# main_board.net
KiCad netlist of a schematic drawn in EAGLE
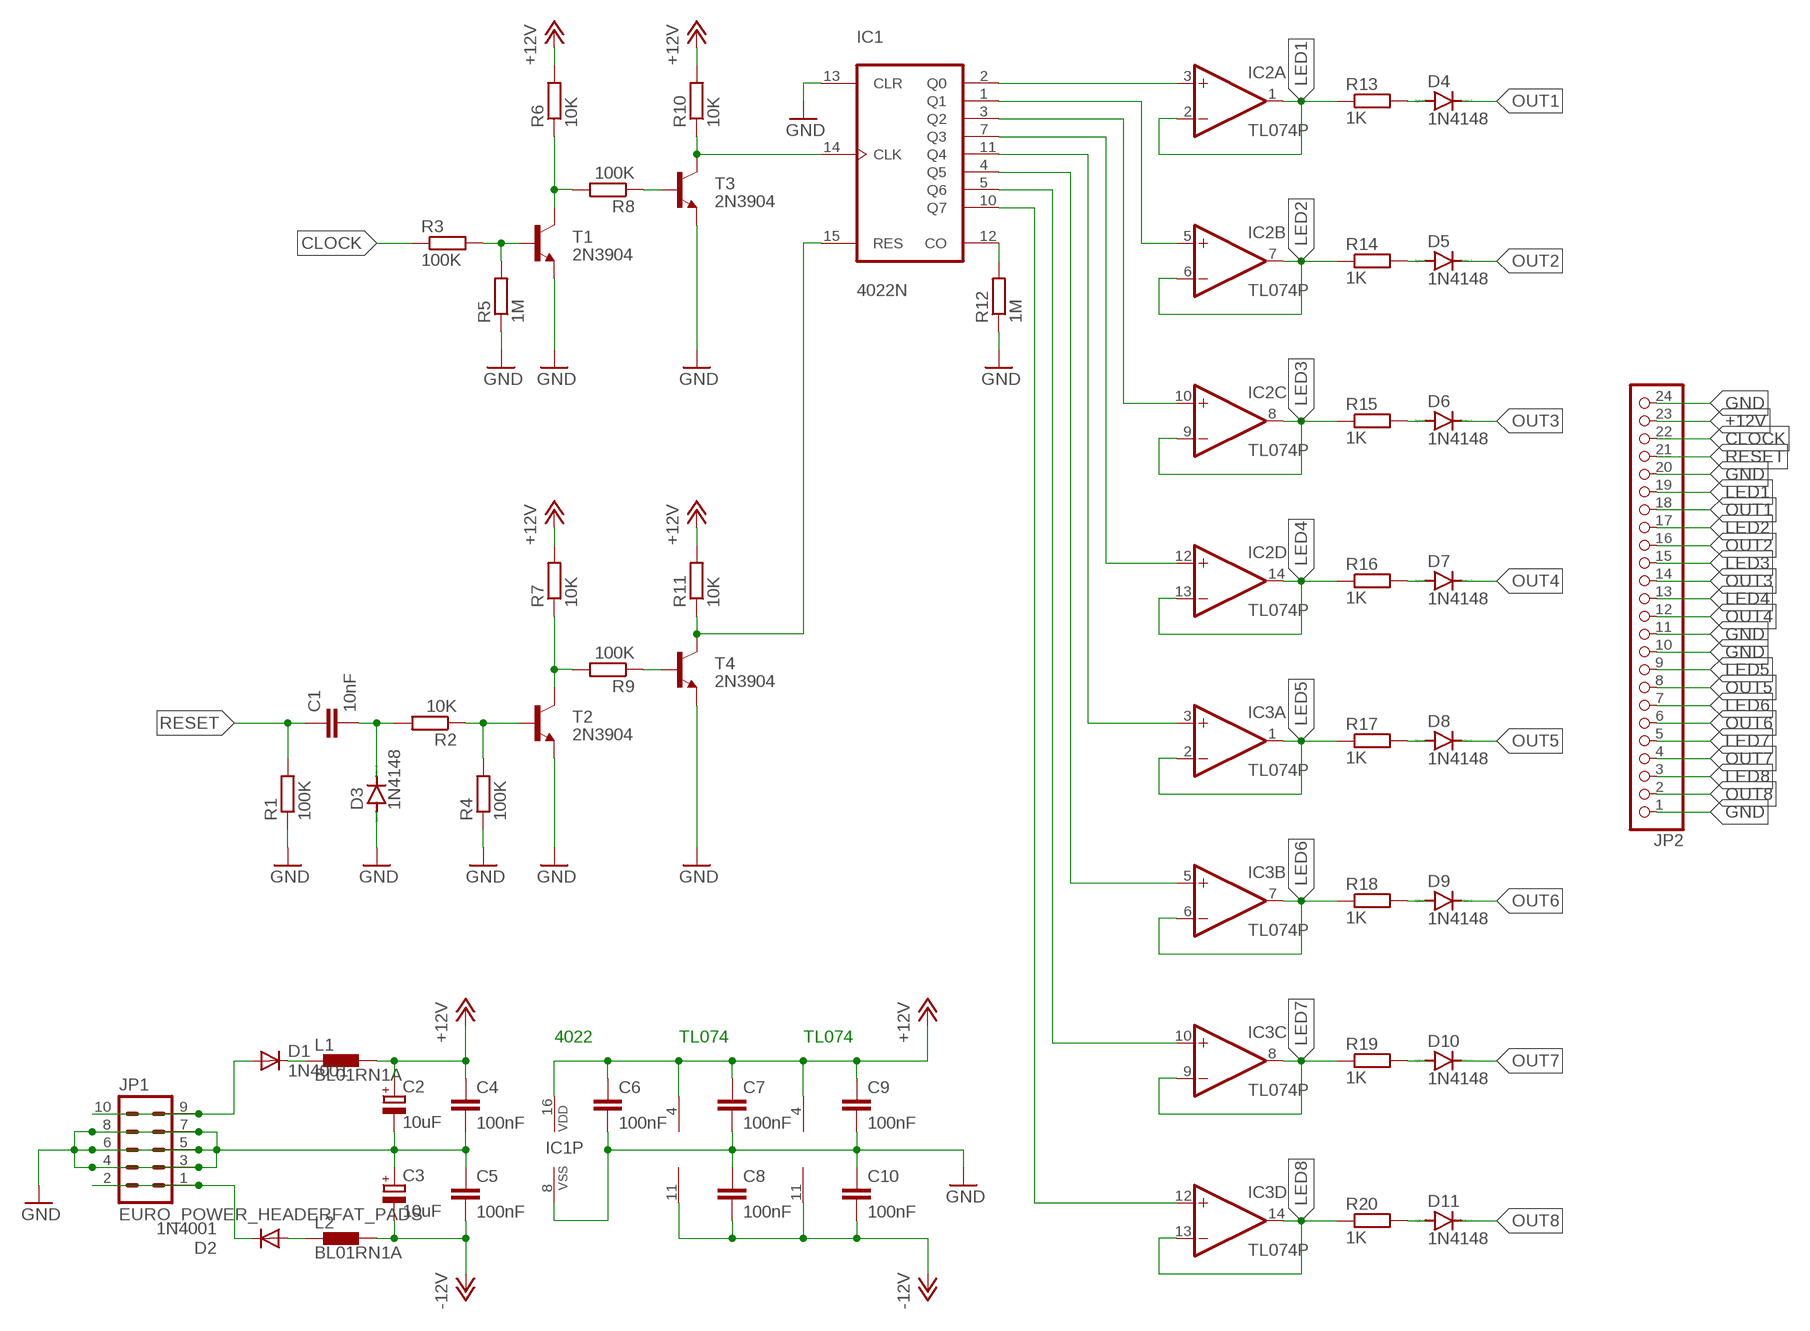
[diagram p0: schematic, sheet 1]

(export (version "E")
  (design (tool "Eeschema 10.0.6"))
  (components
    (comp (ref "C1")
      (value "10nF")
      (footprint "eagle-import:C025-024X044")
      (fields (field (name "MF") "MULTICOMP") (field (name "MPN") "MC0805Y103M500A2.54MM"))
      (libsource (lib "eagle-import") (part "C-EU025-024X044"))
    )
    (comp (ref "C2")
      (value "10uF")
      (footprint "eagle-import:E2,5-6E")
      (fields (field (name "MF") "RUBYCON") (field (name "MPN") "35ZLG10MEFC5X7"))
      (libsource (lib "eagle-import") (part "CPOL-EUE2,5-6E"))
    )
    (comp (ref "C3")
      (value "10uF")
      (footprint "eagle-import:E2,5-6E")
      (fields (field (name "MF") "RUBYCON") (field (name "MPN") "35ZLG10MEFC5X7"))
      (libsource (lib "eagle-import") (part "CPOL-EUE2,5-6E"))
    )
    (comp (ref "C4")
      (value "100nF")
      (footprint "eagle-import:C025-024X044")
      (fields (field (name "MF") "EPCOS") (field (name "MPN") "B32529C0104J289"))
      (libsource (lib "eagle-import") (part "C-EU025-024X044"))
    )
    (comp (ref "C5")
      (value "100nF")
      (footprint "eagle-import:C025-024X044")
      (fields (field (name "MF") "EPCOS") (field (name "MPN") "B32529C0104J289"))
      (libsource (lib "eagle-import") (part "C-EU025-024X044"))
    )
    (comp (ref "C6")
      (value "100nF")
      (footprint "eagle-import:C025-024X044")
      (fields (field (name "MF") "EPCOS") (field (name "MPN") "B32529C0104J289"))
      (libsource (lib "eagle-import") (part "C-EU025-024X044"))
    )
    (comp (ref "C7")
      (value "100nF")
      (footprint "eagle-import:C025-024X044")
      (fields (field (name "MF") "EPCOS") (field (name "MPN") "B32529C0104J289"))
      (libsource (lib "eagle-import") (part "C-EU025-024X044"))
    )
    (comp (ref "C8")
      (value "100nF")
      (footprint "eagle-import:C025-024X044")
      (fields (field (name "MF") "EPCOS") (field (name "MPN") "B32529C0104J289"))
      (libsource (lib "eagle-import") (part "C-EU025-024X044"))
    )
    (comp (ref "C9")
      (value "100nF")
      (footprint "eagle-import:C025-024X044")
      (fields (field (name "MF") "EPCOS") (field (name "MPN") "B32529C0104J289"))
      (libsource (lib "eagle-import") (part "C-EU025-024X044"))
    )
    (comp (ref "C10")
      (value "100nF")
      (footprint "eagle-import:C025-024X044")
      (fields (field (name "MF") "EPCOS") (field (name "MPN") "B32529C0104J289"))
      (libsource (lib "eagle-import") (part "C-EU025-024X044"))
    )
    (comp (ref "D1")
      (value "1N4001")
      (footprint "eagle-import:DO41-10")
      (fields (field (name "MF") "VISHAY") (field (name "MPN") "1N4001-E3/54"))
      (libsource (lib "eagle-import") (part "1N4004"))
    )
    (comp (ref "D2")
      (value "1N4001")
      (footprint "eagle-import:DO41-10")
      (fields (field (name "MF") "VISHAY") (field (name "MPN") "1N4001-E3/54"))
      (libsource (lib "eagle-import") (part "1N4004"))
    )
    (comp (ref "D3")
      (value "1N4148")
      (footprint "eagle-import:DO35-7")
      (fields (field (name "MF") "DIODES INC.") (field (name "MPN") "1N5817-T"))
      (libsource (lib "eagle-import") (part "1N4148DO35-7"))
    )
    (comp (ref "D4")
      (value "1N4148")
      (footprint "eagle-import:DO35-7")
      (fields (field (name "MF") "DIODES INC.") (field (name "MPN") "1N5817-T"))
      (libsource (lib "eagle-import") (part "1N4148DO35-7"))
    )
    (comp (ref "D5")
      (value "1N4148")
      (footprint "eagle-import:DO35-7")
      (fields (field (name "MF") "DIODES INC.") (field (name "MPN") "1N5817-T"))
      (libsource (lib "eagle-import") (part "1N4148DO35-7"))
    )
    (comp (ref "D6")
      (value "1N4148")
      (footprint "eagle-import:DO35-7")
      (fields (field (name "MF") "DIODES INC.") (field (name "MPN") "1N5817-T"))
      (libsource (lib "eagle-import") (part "1N4148DO35-7"))
    )
    (comp (ref "D7")
      (value "1N4148")
      (footprint "eagle-import:DO35-7")
      (fields (field (name "MF") "DIODES INC.") (field (name "MPN") "1N5817-T"))
      (libsource (lib "eagle-import") (part "1N4148DO35-7"))
    )
    (comp (ref "D8")
      (value "1N4148")
      (footprint "eagle-import:DO35-7")
      (fields (field (name "MF") "DIODES INC.") (field (name "MPN") "1N5817-T"))
      (libsource (lib "eagle-import") (part "1N4148DO35-7"))
    )
    (comp (ref "D9")
      (value "1N4148")
      (footprint "eagle-import:DO35-7")
      (fields (field (name "MF") "DIODES INC.") (field (name "MPN") "1N5817-T"))
      (libsource (lib "eagle-import") (part "1N4148DO35-7"))
    )
    (comp (ref "D10")
      (value "1N4148")
      (footprint "eagle-import:DO35-7")
      (fields (field (name "MF") "DIODES INC.") (field (name "MPN") "1N5817-T"))
      (libsource (lib "eagle-import") (part "1N4148DO35-7"))
    )
    (comp (ref "D11")
      (value "1N4148")
      (footprint "eagle-import:DO35-7")
      (fields (field (name "MF") "DIODES INC.") (field (name "MPN") "1N5817-T"))
      (libsource (lib "eagle-import") (part "1N4148DO35-7"))
    )
    (comp (ref "IC1")
      (value "4022N")
      (footprint "eagle-import:DIL16")
      (fields
        (field (name "MF") "TEXAS INSTRUMENTS")
        (field (name "MPN") "CD4022BE")
        (field (name "OC_FARNELL") "3006269")
      )
      (libsource (lib "eagle-import") (part "4022N"))
    )
    (comp (ref "IC2")
      (value "TL074P")
      (footprint "eagle-import:DIL14")
      (fields
        (field (name "MF") "TEXAS INSTRUMENTS")
        (field (name "MPN") "TL074ACN")
        (field (name "OC_FARNELL") "3117798")
      )
      (libsource (lib "eagle-import") (part "TL074P"))
    )
    (comp (ref "IC3")
      (value "TL074P")
      (footprint "eagle-import:DIL14")
      (fields
        (field (name "MF") "TEXAS INSTRUMENTS")
        (field (name "MPN") "TL074ACN")
        (field (name "OC_FARNELL") "3117798")
      )
      (libsource (lib "eagle-import") (part "TL074P"))
    )
    (comp (ref "JP1")
      (value "EURO_POWER_HEADERFAT_PADS")
      (footprint "eagle-import:EURO_PWR_HEADER_FAT")
      (libsource (lib "eagle-import") (part "EURO_POWER_HEADERFAT_PADS"))
    )
    (comp (ref "JP2")
      (value "PINHD-1X24/90")
      (footprint "eagle-import:1X24_90")
      (libsource (lib "eagle-import") (part "PINHD-1X24/90"))
    )
    (comp (ref "L1")
      (value "BL01RN1A")
      (footprint "eagle-import:BL01RN1A")
      (libsource (lib "eagle-import") (part "BL01RN1A"))
    )
    (comp (ref "L2")
      (value "BL01RN1A")
      (footprint "eagle-import:BL01RN1A")
      (libsource (lib "eagle-import") (part "BL01RN1A"))
    )
    (comp (ref "R1")
      (value "100K")
      (footprint "eagle-import:0204_5")
      (fields (field (name "MF") "MULTICOMP PRO") (field (name "MPN") "MCF 0.25W 100K"))
      (libsource (lib "eagle-import") (part "R-EU_0204/5"))
    )
    (comp (ref "R2")
      (value "10K")
      (footprint "eagle-import:0204_5")
      (fields (field (name "MF") "MULTICOMP PRO") (field (name "MPN") "MCF 0.25W 10K"))
      (libsource (lib "eagle-import") (part "R-EU_0204/5"))
    )
    (comp (ref "R3")
      (value "100K")
      (footprint "eagle-import:0204_5")
      (fields (field (name "MF") "MULTICOMP PRO") (field (name "MPN") "MCF 0.25W 100K"))
      (libsource (lib "eagle-import") (part "R-EU_0204/5"))
    )
    (comp (ref "R4")
      (value "100K")
      (footprint "eagle-import:0204_5")
      (fields (field (name "MF") "MULTICOMP PRO") (field (name "MPN") "MCF 0.25W 100K"))
      (libsource (lib "eagle-import") (part "R-EU_0204/5"))
    )
    (comp (ref "R5")
      (value "1M")
      (footprint "eagle-import:0204_5")
      (fields (field (name "MF") "MULTICOMP PRO") (field (name "MPN") "MCF 0.25W 1M"))
      (libsource (lib "eagle-import") (part "R-EU_0204/5"))
    )
    (comp (ref "R6")
      (value "10K")
      (footprint "eagle-import:0204_5")
      (fields (field (name "MF") "MULTICOMP PRO") (field (name "MPN") "MCF 0.25W 10K"))
      (libsource (lib "eagle-import") (part "R-EU_0204/5"))
    )
    (comp (ref "R7")
      (value "10K")
      (footprint "eagle-import:0204_5")
      (fields (field (name "MF") "MULTICOMP PRO") (field (name "MPN") "MCF 0.25W 10K"))
      (libsource (lib "eagle-import") (part "R-EU_0204/5"))
    )
    (comp (ref "R8")
      (value "100K")
      (footprint "eagle-import:0204_5")
      (fields (field (name "MF") "MULTICOMP PRO") (field (name "MPN") "MCF 0.25W 100K"))
      (libsource (lib "eagle-import") (part "R-EU_0204/5"))
    )
    (comp (ref "R9")
      (value "100K")
      (footprint "eagle-import:0204_5")
      (fields (field (name "MF") "MULTICOMP PRO") (field (name "MPN") "MCF 0.25W 100K"))
      (libsource (lib "eagle-import") (part "R-EU_0204/5"))
    )
    (comp (ref "R10")
      (value "10K")
      (footprint "eagle-import:0204_5")
      (fields (field (name "MF") "MULTICOMP PRO") (field (name "MPN") "MCF 0.25W 10K"))
      (libsource (lib "eagle-import") (part "R-EU_0204/5"))
    )
    (comp (ref "R11")
      (value "10K")
      (footprint "eagle-import:0204_5")
      (fields (field (name "MF") "MULTICOMP PRO") (field (name "MPN") "MCF 0.25W 10K"))
      (libsource (lib "eagle-import") (part "R-EU_0204/5"))
    )
    (comp (ref "R12")
      (value "1M")
      (footprint "eagle-import:0204_5")
      (fields (field (name "MF") "MULTICOMP PRO") (field (name "MPN") "MCF 0.25W 1M"))
      (libsource (lib "eagle-import") (part "R-EU_0204/5"))
    )
    (comp (ref "R13")
      (value "1K")
      (footprint "eagle-import:0204_5")
      (fields (field (name "MF") "MULTICOMP PRO") (field (name "MPN") "MCF 0.25W 1K"))
      (libsource (lib "eagle-import") (part "R-EU_0204/5"))
    )
    (comp (ref "R14")
      (value "1K")
      (footprint "eagle-import:0204_5")
      (fields (field (name "MF") "MULTICOMP PRO") (field (name "MPN") "MCF 0.25W 1K"))
      (libsource (lib "eagle-import") (part "R-EU_0204/5"))
    )
    (comp (ref "R15")
      (value "1K")
      (footprint "eagle-import:0204_5")
      (fields (field (name "MF") "MULTICOMP PRO") (field (name "MPN") "MCF 0.25W 1K"))
      (libsource (lib "eagle-import") (part "R-EU_0204/5"))
    )
    (comp (ref "R16")
      (value "1K")
      (footprint "eagle-import:0204_5")
      (fields (field (name "MF") "MULTICOMP PRO") (field (name "MPN") "MCF 0.25W 1K"))
      (libsource (lib "eagle-import") (part "R-EU_0204/5"))
    )
    (comp (ref "R17")
      (value "1K")
      (footprint "eagle-import:0204_5")
      (fields (field (name "MF") "MULTICOMP PRO") (field (name "MPN") "MCF 0.25W 1K"))
      (libsource (lib "eagle-import") (part "R-EU_0204/5"))
    )
    (comp (ref "R18")
      (value "1K")
      (footprint "eagle-import:0204_5")
      (fields (field (name "MF") "MULTICOMP PRO") (field (name "MPN") "MCF 0.25W 1K"))
      (libsource (lib "eagle-import") (part "R-EU_0204/5"))
    )
    (comp (ref "R19")
      (value "1K")
      (footprint "eagle-import:0204_5")
      (fields (field (name "MF") "MULTICOMP PRO") (field (name "MPN") "MCF 0.25W 1K"))
      (libsource (lib "eagle-import") (part "R-EU_0204/5"))
    )
    (comp (ref "R20")
      (value "1K")
      (footprint "eagle-import:0204_5")
      (fields (field (name "MF") "MULTICOMP PRO") (field (name "MPN") "MCF 0.25W 1K"))
      (libsource (lib "eagle-import") (part "R-EU_0204/5"))
    )
    (comp (ref "T1")
      (value "2N3904")
      (footprint "eagle-import:TO92")
      (fields (field (name "MF") "MULTICOMP PRO"))
      (libsource (lib "eagle-import") (part "2N3904"))
    )
    (comp (ref "T2")
      (value "2N3904")
      (footprint "eagle-import:TO92")
      (fields (field (name "MF") "MULTICOMP PRO"))
      (libsource (lib "eagle-import") (part "2N3904"))
    )
    (comp (ref "T3")
      (value "2N3904")
      (footprint "eagle-import:TO92")
      (fields (field (name "MF") "MULTICOMP PRO"))
      (libsource (lib "eagle-import") (part "2N3904"))
    )
    (comp (ref "T4")
      (value "2N3904")
      (footprint "eagle-import:TO92")
      (fields (field (name "MF") "MULTICOMP PRO"))
      (libsource (lib "eagle-import") (part "2N3904"))
    )
  )
  (nets
    (net (code "1") (name "+12V") (class "Default")
      (node (ref "C2") (pin "+") (pinfunction "+_+") (pintype "passive"))
      (node (ref "C4") (pin "1") (pinfunction "1_1") (pintype "passive"))
      (node (ref "C6") (pin "1") (pinfunction "1_1") (pintype "passive"))
      (node (ref "C7") (pin "1") (pinfunction "1_1") (pintype "passive"))
      (node (ref "C9") (pin "1") (pinfunction "1_1") (pintype "passive"))
      (node (ref "IC1") (pin "16") (pinfunction "VDD_16") (pintype "power_in"))
      (node (ref "IC2") (pin "4") (pinfunction "V+_4") (pintype "power_in"))
      (node (ref "IC3") (pin "4") (pinfunction "V+_4") (pintype "power_in"))
      (node (ref "JP2") (pin "23") (pinfunction "23_23") (pintype "passive"))
      (node (ref "L1") (pin "2") (pinfunction "2_2") (pintype "passive"))
      (node (ref "R10") (pin "2") (pinfunction "2_2") (pintype "passive"))
      (node (ref "R11") (pin "2") (pinfunction "2_2") (pintype "passive"))
      (node (ref "R6") (pin "2") (pinfunction "2_2") (pintype "passive"))
      (node (ref "R7") (pin "2") (pinfunction "2_2") (pintype "passive"))
    )
    (net (code "2") (name "-12V") (class "Default")
      (node (ref "C10") (pin "2") (pinfunction "2_2") (pintype "passive"))
      (node (ref "C3") (pin "-") (pinfunction "-_-") (pintype "passive"))
      (node (ref "C5") (pin "2") (pinfunction "2_2") (pintype "passive"))
      (node (ref "C8") (pin "2") (pinfunction "2_2") (pintype "passive"))
      (node (ref "IC2") (pin "11") (pinfunction "V-_11") (pintype "power_in"))
      (node (ref "IC3") (pin "11") (pinfunction "V-_11") (pintype "power_in"))
      (node (ref "L2") (pin "2") (pinfunction "2_2") (pintype "passive"))
    )
    (net (code "3") (name "CLOCK") (class "Default")
      (node (ref "JP2") (pin "22") (pinfunction "22_22") (pintype "passive"))
      (node (ref "R3") (pin "1") (pinfunction "1_1") (pintype "passive"))
    )
    (net (code "4") (name "GND") (class "Default")
      (node (ref "C10") (pin "1") (pinfunction "1_1") (pintype "passive"))
      (node (ref "C2") (pin "-") (pinfunction "-_-") (pintype "passive"))
      (node (ref "C3") (pin "+") (pinfunction "+_+") (pintype "passive"))
      (node (ref "C4") (pin "2") (pinfunction "2_2") (pintype "passive"))
      (node (ref "C5") (pin "1") (pinfunction "1_1") (pintype "passive"))
      (node (ref "C6") (pin "2") (pinfunction "2_2") (pintype "passive"))
      (node (ref "C7") (pin "2") (pinfunction "2_2") (pintype "passive"))
      (node (ref "C8") (pin "1") (pinfunction "1_1") (pintype "passive"))
      (node (ref "C9") (pin "2") (pinfunction "2_2") (pintype "passive"))
      (node (ref "D3") (pin "A") (pinfunction "A_A") (pintype "passive"))
      (node (ref "IC1") (pin "13") (pinfunction "CLR_13") (pintype "input"))
      (node (ref "IC1") (pin "8") (pinfunction "VSS_8") (pintype "power_in"))
      (node (ref "JP1") (pin "3") (pinfunction "3_3") (pintype "passive"))
      (node (ref "JP1") (pin "4") (pinfunction "4_4") (pintype "passive"))
      (node (ref "JP1") (pin "5") (pinfunction "5_5") (pintype "passive"))
      (node (ref "JP1") (pin "6") (pinfunction "6_6") (pintype "passive"))
      (node (ref "JP1") (pin "7") (pinfunction "7_7") (pintype "passive"))
      (node (ref "JP1") (pin "8") (pinfunction "8_8") (pintype "passive"))
      (node (ref "JP2") (pin "1") (pinfunction "1_1") (pintype "passive"))
      (node (ref "JP2") (pin "10") (pinfunction "10_10") (pintype "passive"))
      (node (ref "JP2") (pin "11") (pinfunction "11_11") (pintype "passive"))
      (node (ref "JP2") (pin "20") (pinfunction "20_20") (pintype "passive"))
      (node (ref "JP2") (pin "24") (pinfunction "24_24") (pintype "passive"))
      (node (ref "R1") (pin "1") (pinfunction "1_1") (pintype "passive"))
      (node (ref "R12") (pin "1") (pinfunction "1_1") (pintype "passive"))
      (node (ref "R4") (pin "1") (pinfunction "1_1") (pintype "passive"))
      (node (ref "R5") (pin "1") (pinfunction "1_1") (pintype "passive"))
      (node (ref "T1") (pin "3") (pinfunction "E_3") (pintype "passive"))
      (node (ref "T2") (pin "3") (pinfunction "E_3") (pintype "passive"))
      (node (ref "T3") (pin "3") (pinfunction "E_3") (pintype "passive"))
      (node (ref "T4") (pin "3") (pinfunction "E_3") (pintype "passive"))
    )
    (net (code "5") (name "LED1") (class "Default")
      (node (ref "IC2") (pin "1") (pinfunction "OUT_1") (pintype "output"))
      (node (ref "IC2") (pin "2") (pinfunction "-IN_2") (pintype "input"))
      (node (ref "JP2") (pin "19") (pinfunction "19_19") (pintype "passive"))
      (node (ref "R13") (pin "1") (pinfunction "1_1") (pintype "passive"))
    )
    (net (code "6") (name "LED2") (class "Default")
      (node (ref "IC2") (pin "6") (pinfunction "-IN_6") (pintype "input"))
      (node (ref "IC2") (pin "7") (pinfunction "OUT_7") (pintype "output"))
      (node (ref "JP2") (pin "17") (pinfunction "17_17") (pintype "passive"))
      (node (ref "R14") (pin "1") (pinfunction "1_1") (pintype "passive"))
    )
    (net (code "7") (name "LED3") (class "Default")
      (node (ref "IC2") (pin "8") (pinfunction "OUT_8") (pintype "output"))
      (node (ref "IC2") (pin "9") (pinfunction "-IN_9") (pintype "input"))
      (node (ref "JP2") (pin "15") (pinfunction "15_15") (pintype "passive"))
      (node (ref "R15") (pin "1") (pinfunction "1_1") (pintype "passive"))
    )
    (net (code "8") (name "LED4") (class "Default")
      (node (ref "IC2") (pin "13") (pinfunction "-IN_13") (pintype "input"))
      (node (ref "IC2") (pin "14") (pinfunction "OUT_14") (pintype "output"))
      (node (ref "JP2") (pin "13") (pinfunction "13_13") (pintype "passive"))
      (node (ref "R16") (pin "1") (pinfunction "1_1") (pintype "passive"))
    )
    (net (code "9") (name "LED5") (class "Default")
      (node (ref "IC3") (pin "1") (pinfunction "OUT_1") (pintype "output"))
      (node (ref "IC3") (pin "2") (pinfunction "-IN_2") (pintype "input"))
      (node (ref "JP2") (pin "9") (pinfunction "9_9") (pintype "passive"))
      (node (ref "R17") (pin "1") (pinfunction "1_1") (pintype "passive"))
    )
    (net (code "10") (name "LED6") (class "Default")
      (node (ref "IC3") (pin "6") (pinfunction "-IN_6") (pintype "input"))
      (node (ref "IC3") (pin "7") (pinfunction "OUT_7") (pintype "output"))
      (node (ref "JP2") (pin "7") (pinfunction "7_7") (pintype "passive"))
      (node (ref "R18") (pin "1") (pinfunction "1_1") (pintype "passive"))
    )
    (net (code "11") (name "LED7") (class "Default")
      (node (ref "IC3") (pin "8") (pinfunction "OUT_8") (pintype "output"))
      (node (ref "IC3") (pin "9") (pinfunction "-IN_9") (pintype "input"))
      (node (ref "JP2") (pin "5") (pinfunction "5_5") (pintype "passive"))
      (node (ref "R19") (pin "1") (pinfunction "1_1") (pintype "passive"))
    )
    (net (code "12") (name "LED8") (class "Default")
      (node (ref "IC3") (pin "13") (pinfunction "-IN_13") (pintype "input"))
      (node (ref "IC3") (pin "14") (pinfunction "OUT_14") (pintype "output"))
      (node (ref "JP2") (pin "3") (pinfunction "3_3") (pintype "passive"))
      (node (ref "R20") (pin "1") (pinfunction "1_1") (pintype "passive"))
    )
    (net (code "13") (name "Net-(C1-Pad2)") (class "Default")
      (node (ref "C1") (pin "2") (pinfunction "2_2") (pintype "passive"))
      (node (ref "D3") (pin "C") (pinfunction "C_C") (pintype "passive"))
      (node (ref "R2") (pin "2") (pinfunction "2_2") (pintype "passive"))
    )
    (net (code "14") (name "Net-(D1-PadA)") (class "Default")
      (node (ref "D1") (pin "A") (pinfunction "A_A") (pintype "passive"))
      (node (ref "JP1") (pin "10") (pinfunction "10_10") (pintype "passive"))
      (node (ref "JP1") (pin "9") (pinfunction "9_9") (pintype "passive"))
    )
    (net (code "15") (name "Net-(D1-PadC)") (class "Default")
      (node (ref "D1") (pin "C") (pinfunction "C_C") (pintype "passive"))
      (node (ref "L1") (pin "1") (pinfunction "1_1") (pintype "passive"))
    )
    (net (code "16") (name "Net-(D2-PadA)") (class "Default")
      (node (ref "D2") (pin "A") (pinfunction "A_A") (pintype "passive"))
      (node (ref "L2") (pin "1") (pinfunction "1_1") (pintype "passive"))
    )
    (net (code "17") (name "Net-(D2-PadC)") (class "Default")
      (node (ref "D2") (pin "C") (pinfunction "C_C") (pintype "passive"))
      (node (ref "JP1") (pin "1") (pinfunction "1_1") (pintype "passive"))
      (node (ref "JP1") (pin "2") (pinfunction "2_2") (pintype "passive"))
    )
    (net (code "18") (name "Net-(D4-PadA)") (class "Default")
      (node (ref "D4") (pin "A") (pinfunction "A_A") (pintype "passive"))
      (node (ref "R13") (pin "2") (pinfunction "2_2") (pintype "passive"))
    )
    (net (code "19") (name "Net-(D5-PadA)") (class "Default")
      (node (ref "D5") (pin "A") (pinfunction "A_A") (pintype "passive"))
      (node (ref "R14") (pin "2") (pinfunction "2_2") (pintype "passive"))
    )
    (net (code "20") (name "Net-(D6-PadA)") (class "Default")
      (node (ref "D6") (pin "A") (pinfunction "A_A") (pintype "passive"))
      (node (ref "R15") (pin "2") (pinfunction "2_2") (pintype "passive"))
    )
    (net (code "21") (name "Net-(D7-PadA)") (class "Default")
      (node (ref "D7") (pin "A") (pinfunction "A_A") (pintype "passive"))
      (node (ref "R16") (pin "2") (pinfunction "2_2") (pintype "passive"))
    )
    (net (code "22") (name "Net-(D8-PadA)") (class "Default")
      (node (ref "D8") (pin "A") (pinfunction "A_A") (pintype "passive"))
      (node (ref "R17") (pin "2") (pinfunction "2_2") (pintype "passive"))
    )
    (net (code "23") (name "Net-(D9-PadA)") (class "Default")
      (node (ref "D9") (pin "A") (pinfunction "A_A") (pintype "passive"))
      (node (ref "R18") (pin "2") (pinfunction "2_2") (pintype "passive"))
    )
    (net (code "24") (name "Net-(D10-PadA)") (class "Default")
      (node (ref "D10") (pin "A") (pinfunction "A_A") (pintype "passive"))
      (node (ref "R19") (pin "2") (pinfunction "2_2") (pintype "passive"))
    )
    (net (code "25") (name "Net-(D11-PadA)") (class "Default")
      (node (ref "D11") (pin "A") (pinfunction "A_A") (pintype "passive"))
      (node (ref "R20") (pin "2") (pinfunction "2_2") (pintype "passive"))
    )
    (net (code "26") (name "Net-(IC1A-CLK)") (class "Default")
      (node (ref "IC1") (pin "14") (pinfunction "CLK_14") (pintype "input"))
      (node (ref "R10") (pin "1") (pinfunction "1_1") (pintype "passive"))
      (node (ref "T3") (pin "1") (pinfunction "C_1") (pintype "passive"))
    )
    (net (code "27") (name "Net-(IC1A-CO)") (class "Default")
      (node (ref "IC1") (pin "12") (pinfunction "CO_12") (pintype "output"))
      (node (ref "R12") (pin "2") (pinfunction "2_2") (pintype "passive"))
    )
    (net (code "28") (name "Net-(IC1A-Q0)") (class "Default")
      (node (ref "IC1") (pin "2") (pinfunction "Q0_2") (pintype "output"))
      (node (ref "IC2") (pin "3") (pinfunction "+IN_3") (pintype "input"))
    )
    (net (code "29") (name "Net-(IC1A-Q1)") (class "Default")
      (node (ref "IC1") (pin "1") (pinfunction "Q1_1") (pintype "output"))
      (node (ref "IC2") (pin "5") (pinfunction "+IN_5") (pintype "input"))
    )
    (net (code "30") (name "Net-(IC1A-Q2)") (class "Default")
      (node (ref "IC1") (pin "3") (pinfunction "Q2_3") (pintype "output"))
      (node (ref "IC2") (pin "10") (pinfunction "+IN_10") (pintype "input"))
    )
    (net (code "31") (name "Net-(IC1A-Q3)") (class "Default")
      (node (ref "IC1") (pin "7") (pinfunction "Q3_7") (pintype "output"))
      (node (ref "IC2") (pin "12") (pinfunction "+IN_12") (pintype "input"))
    )
    (net (code "32") (name "Net-(IC1A-Q4)") (class "Default")
      (node (ref "IC1") (pin "11") (pinfunction "Q4_11") (pintype "output"))
      (node (ref "IC3") (pin "3") (pinfunction "+IN_3") (pintype "input"))
    )
    (net (code "33") (name "Net-(IC1A-Q5)") (class "Default")
      (node (ref "IC1") (pin "4") (pinfunction "Q5_4") (pintype "output"))
      (node (ref "IC3") (pin "5") (pinfunction "+IN_5") (pintype "input"))
    )
    (net (code "34") (name "Net-(IC1A-Q6)") (class "Default")
      (node (ref "IC1") (pin "5") (pinfunction "Q6_5") (pintype "output"))
      (node (ref "IC3") (pin "10") (pinfunction "+IN_10") (pintype "input"))
    )
    (net (code "35") (name "Net-(IC1A-Q7)") (class "Default")
      (node (ref "IC1") (pin "10") (pinfunction "Q7_10") (pintype "output"))
      (node (ref "IC3") (pin "12") (pinfunction "+IN_12") (pintype "input"))
    )
    (net (code "36") (name "Net-(IC1A-RES)") (class "Default")
      (node (ref "IC1") (pin "15") (pinfunction "RES_15") (pintype "input"))
      (node (ref "R11") (pin "1") (pinfunction "1_1") (pintype "passive"))
      (node (ref "T4") (pin "1") (pinfunction "C_1") (pintype "passive"))
    )
    (net (code "37") (name "Net-(T1-B)") (class "Default")
      (node (ref "R3") (pin "2") (pinfunction "2_2") (pintype "passive"))
      (node (ref "R5") (pin "2") (pinfunction "2_2") (pintype "passive"))
      (node (ref "T1") (pin "2") (pinfunction "B_2") (pintype "passive"))
    )
    (net (code "38") (name "Net-(T1-C)") (class "Default")
      (node (ref "R6") (pin "1") (pinfunction "1_1") (pintype "passive"))
      (node (ref "R8") (pin "2") (pinfunction "2_2") (pintype "passive"))
      (node (ref "T1") (pin "1") (pinfunction "C_1") (pintype "passive"))
    )
    (net (code "39") (name "Net-(T2-B)") (class "Default")
      (node (ref "R2") (pin "1") (pinfunction "1_1") (pintype "passive"))
      (node (ref "R4") (pin "2") (pinfunction "2_2") (pintype "passive"))
      (node (ref "T2") (pin "2") (pinfunction "B_2") (pintype "passive"))
    )
    (net (code "40") (name "Net-(T2-C)") (class "Default")
      (node (ref "R7") (pin "1") (pinfunction "1_1") (pintype "passive"))
      (node (ref "R9") (pin "2") (pinfunction "2_2") (pintype "passive"))
      (node (ref "T2") (pin "1") (pinfunction "C_1") (pintype "passive"))
    )
    (net (code "41") (name "Net-(T3-B)") (class "Default")
      (node (ref "R8") (pin "1") (pinfunction "1_1") (pintype "passive"))
      (node (ref "T3") (pin "2") (pinfunction "B_2") (pintype "passive"))
    )
    (net (code "42") (name "Net-(T4-B)") (class "Default")
      (node (ref "R9") (pin "1") (pinfunction "1_1") (pintype "passive"))
      (node (ref "T4") (pin "2") (pinfunction "B_2") (pintype "passive"))
    )
    (net (code "43") (name "OUT1") (class "Default")
      (node (ref "D4") (pin "C") (pinfunction "C_C") (pintype "passive"))
      (node (ref "JP2") (pin "18") (pinfunction "18_18") (pintype "passive"))
    )
    (net (code "44") (name "OUT2") (class "Default")
      (node (ref "D5") (pin "C") (pinfunction "C_C") (pintype "passive"))
      (node (ref "JP2") (pin "16") (pinfunction "16_16") (pintype "passive"))
    )
    (net (code "45") (name "OUT3") (class "Default")
      (node (ref "D6") (pin "C") (pinfunction "C_C") (pintype "passive"))
      (node (ref "JP2") (pin "14") (pinfunction "14_14") (pintype "passive"))
    )
    (net (code "46") (name "OUT4") (class "Default")
      (node (ref "D7") (pin "C") (pinfunction "C_C") (pintype "passive"))
      (node (ref "JP2") (pin "12") (pinfunction "12_12") (pintype "passive"))
    )
    (net (code "47") (name "OUT5") (class "Default")
      (node (ref "D8") (pin "C") (pinfunction "C_C") (pintype "passive"))
      (node (ref "JP2") (pin "8") (pinfunction "8_8") (pintype "passive"))
    )
    (net (code "48") (name "OUT6") (class "Default")
      (node (ref "D9") (pin "C") (pinfunction "C_C") (pintype "passive"))
      (node (ref "JP2") (pin "6") (pinfunction "6_6") (pintype "passive"))
    )
    (net (code "49") (name "OUT7") (class "Default")
      (node (ref "D10") (pin "C") (pinfunction "C_C") (pintype "passive"))
      (node (ref "JP2") (pin "4") (pinfunction "4_4") (pintype "passive"))
    )
    (net (code "50") (name "OUT8") (class "Default")
      (node (ref "D11") (pin "C") (pinfunction "C_C") (pintype "passive"))
      (node (ref "JP2") (pin "2") (pinfunction "2_2") (pintype "passive"))
    )
    (net (code "51") (name "RESET") (class "Default")
      (node (ref "C1") (pin "1") (pinfunction "1_1") (pintype "passive"))
      (node (ref "JP2") (pin "21") (pinfunction "21_21") (pintype "passive"))
      (node (ref "R1") (pin "2") (pinfunction "2_2") (pintype "passive"))
    )
  )
)
